# LED.net
KiCad netlist of a schematic drawn in Altium Designer
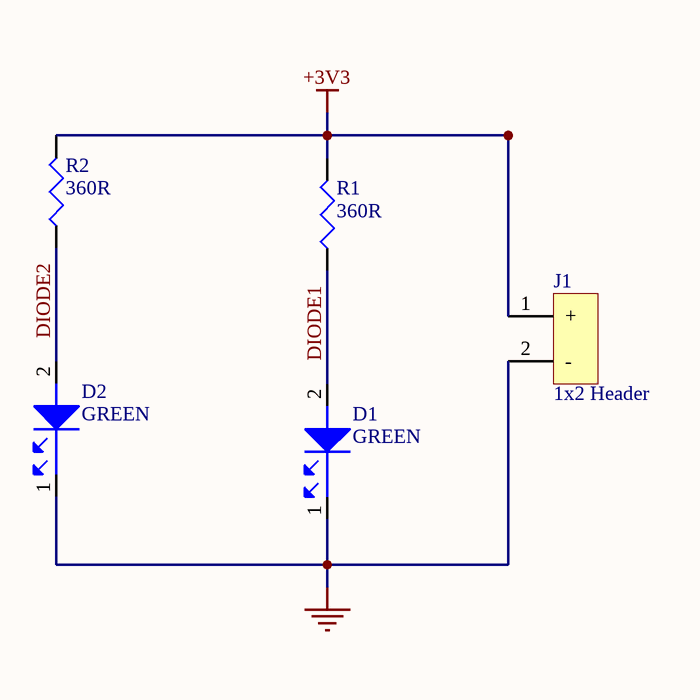
[diagram p0: LED.SchDoc]

(export (version "E")
  (design (tool "Eeschema 10.0.6"))
  (components
    (comp (ref "D1")
      (value "GREEN")
      (footprint "LED0603G")
      (description "LED GREEN ESS II SMD")
      (libsource (lib "LED_SchLib") (part "LNJ337W83RA"))
    )
    (comp (ref "D2")
      (value "GREEN")
      (footprint "LED0603G")
      (description "LED GREEN ESS II SMD")
      (libsource (lib "LED_SchLib") (part "LNJ337W83RA"))
    )
    (comp (ref "J1")
      (value "1x2 Header")
      (footprint "HDR1X2")
      (description "Conn Wire to Board HDR 2 POS 2.54mm Solder ST Thru-Hole Bag")
      (libsource (lib "LED_SchLib") (part "22-29-2021"))
    )
    (comp (ref "R1")
      (value "360R")
      (footprint "R0805")
      (description "RES SMD 360 OHM 1% 1/8W 0805")
      (fields (field (name "TOLERANCE") "1%"))
      (libsource (lib "LED_SchLib") (part "CRCW0805360RFKEA"))
    )
    (comp (ref "R2")
      (value "360R")
      (footprint "R0805")
      (description "RES SMD 360 OHM 1% 1/8W 0805")
      (fields (field (name "TOLERANCE") "1%"))
      (libsource (lib "LED_SchLib") (part "CRCW0805360RFKEA"))
    )
  )
  (nets
    (net (code "1") (name "+3V3") (class "Default")
      (node (ref "J1") (pin "1") (pinfunction "+_1") (pintype "passive"))
      (node (ref "R1") (pin "2") (pinfunction "2_2") (pintype "passive"))
      (node (ref "R2") (pin "2") (pinfunction "2_2") (pintype "passive"))
    )
    (net (code "2") (name "/DIODE1") (class "Default")
      (node (ref "D1") (pin "2") (pinfunction "2_2") (pintype "passive"))
      (node (ref "R1") (pin "1") (pinfunction "1_1") (pintype "passive"))
    )
    (net (code "3") (name "/DIODE2") (class "Default")
      (node (ref "D2") (pin "2") (pinfunction "2_2") (pintype "passive"))
      (node (ref "R2") (pin "1") (pinfunction "1_1") (pintype "passive"))
    )
    (net (code "4") (name "GND") (class "Default")
      (node (ref "D1") (pin "1") (pinfunction "1_1") (pintype "passive"))
      (node (ref "D2") (pin "1") (pinfunction "1_1") (pintype "passive"))
      (node (ref "J1") (pin "2") (pinfunction "-_2") (pintype "passive"))
    )
  )
)
